# receiver.net
KiCad netlist of a schematic drawn in EAGLE
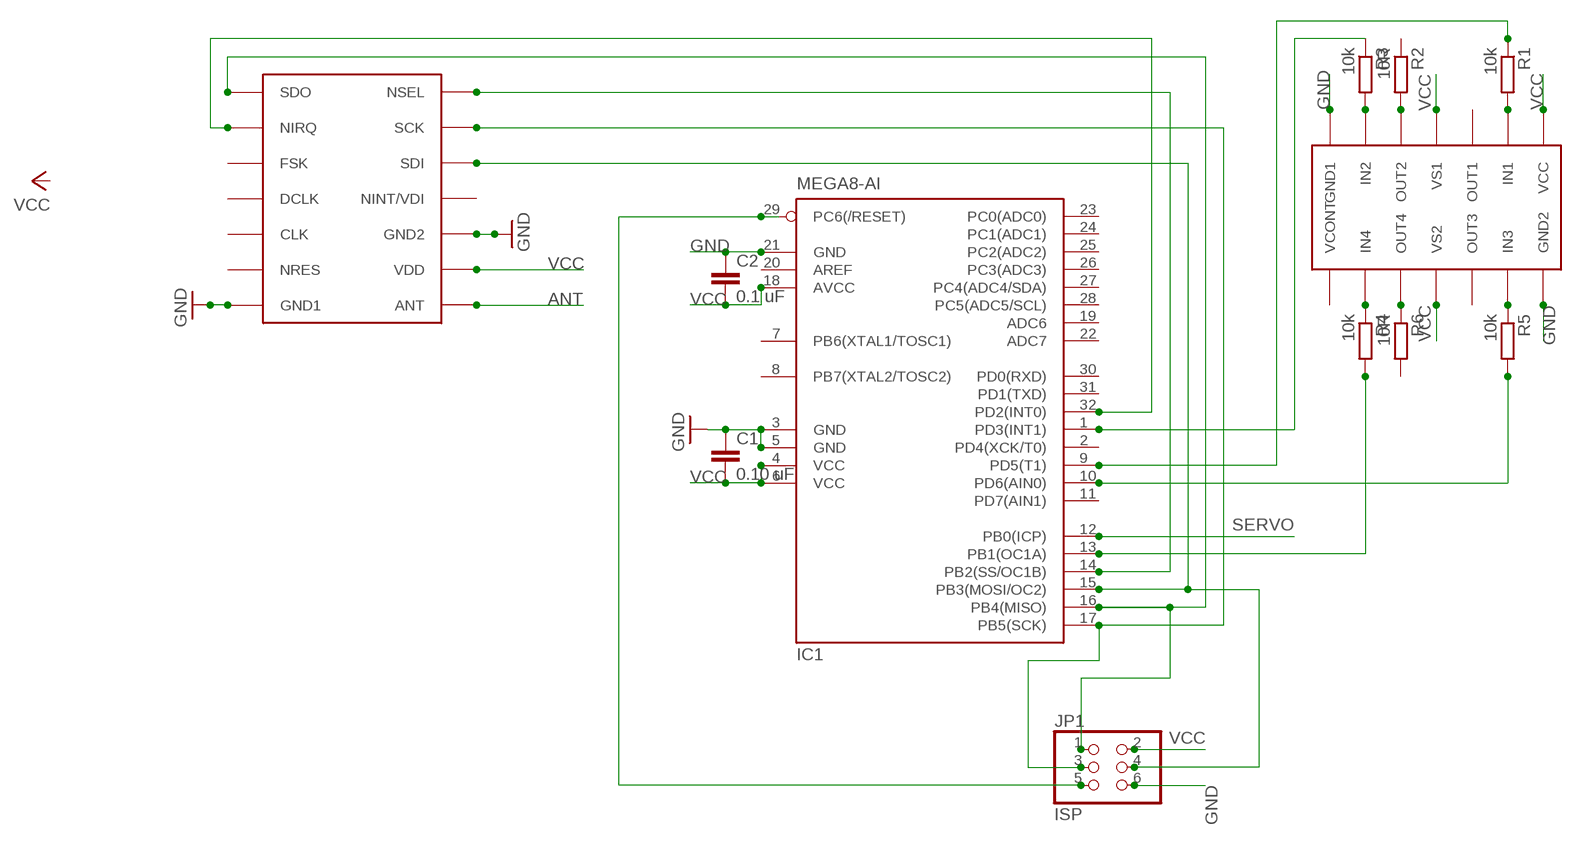
[diagram p0: schematic, sheet 1]

(export (version "E")
  (design (tool "Eeschema 10.0.6"))
  (components
    (comp (ref "C1")
      (value "0.10 uF")
      (footprint "eagle-import:C0805")
      (libsource (lib "eagle-import") (part "C-EUC0805"))
    )
    (comp (ref "C2")
      (value "0.1 uF")
      (footprint "eagle-import:C0805")
      (libsource (lib "eagle-import") (part "C-EUC0805"))
    )
    (comp (ref "IC1")
      (value "MEGA8-AI")
      (footprint "eagle-import:TQFP32-08")
      (fields (field (name "MPN") "ATMEGA8-16AU"))
      (libsource (lib "eagle-import") (part "MEGA8-AI"))
    )
    (comp (ref "JP1")
      (value "ISP")
      (footprint "eagle-import:2X03")
      (libsource (lib "eagle-import") (part "PINHD-2X3"))
    )
    (comp (ref "LB1836M")
      (value "LB1836M")
      (footprint "eagle-import:MFP-14")
      (libsource (lib "eagle-import") (part "LB1836M"))
    )
    (comp (ref "R1")
      (value "10k")
      (footprint "eagle-import:R2012")
      (libsource (lib "eagle-import") (part "R-EU_R2012"))
    )
    (comp (ref "R2")
      (value "10R")
      (footprint "eagle-import:R2012")
      (libsource (lib "eagle-import") (part "R-EU_R2012"))
    )
    (comp (ref "R3")
      (value "10k")
      (footprint "eagle-import:R2012")
      (libsource (lib "eagle-import") (part "R-EU_R2012"))
    )
    (comp (ref "R4")
      (value "10k")
      (footprint "eagle-import:R2012")
      (libsource (lib "eagle-import") (part "R-EU_R2012"))
    )
    (comp (ref "R5")
      (value "10k")
      (footprint "eagle-import:R2012")
      (libsource (lib "eagle-import") (part "R-EU_R2012"))
    )
    (comp (ref "R6")
      (value "10R")
      (footprint "eagle-import:R2012")
      (libsource (lib "eagle-import") (part "R-EU_R2012"))
    )
    (comp (ref "RFM12B")
      (value "RFM12B")
      (footprint "eagle-import:RFM12B")
      (libsource (lib "eagle-import") (part "RFM12B"))
    )
  )
  (nets
    (net (code "1") (name "/ANT") (class "Default")
      (node (ref "RFM12B") (pin "ANT") (pinfunction "ANT_ANT") (pintype "bidirectional"))
    )
    (net (code "2") (name "/SERVO") (class "Default")
      (node (ref "IC1") (pin "12") (pinfunction "PB0(ICP)_12") (pintype "bidirectional"))
    )
    (net (code "3") (name "GND") (class "Default")
      (node (ref "C1") (pin "1") (pinfunction "1_1") (pintype "passive"))
      (node (ref "C2") (pin "1") (pinfunction "1_1") (pintype "passive"))
      (node (ref "IC1") (pin "21") (pinfunction "GND_21") (pintype "power_in"))
      (node (ref "IC1") (pin "3") (pinfunction "GND_3") (pintype "power_in"))
      (node (ref "IC1") (pin "5") (pinfunction "GND_5") (pintype "power_in"))
      (node (ref "JP1") (pin "6") (pinfunction "6_6") (pintype "passive"))
      (node (ref "LB1836M") (pin "GN2") (pinfunction "GND2_GN2") (pintype "bidirectional"))
      (node (ref "LB1836M") (pin "GND1") (pinfunction "GND1_GND1") (pintype "bidirectional"))
      (node (ref "RFM12B") (pin "GND1") (pinfunction "GND1_GND1") (pintype "bidirectional"))
      (node (ref "RFM12B") (pin "GND2") (pinfunction "GND2_GND2") (pintype "bidirectional"))
    )
    (net (code "4") (name "Net-(IC1-PB1(OC1A))") (class "Default")
      (node (ref "IC1") (pin "13") (pinfunction "PB1(OC1A)_13") (pintype "bidirectional"))
      (node (ref "R4") (pin "2") (pinfunction "2_2") (pintype "passive"))
    )
    (net (code "5") (name "Net-(IC1-PB2(SS{slash}OC1B))") (class "Default")
      (node (ref "IC1") (pin "14") (pinfunction "PB2(SS/OC1B)_14") (pintype "bidirectional"))
      (node (ref "RFM12B") (pin "NSEL") (pinfunction "NSEL_NSEL") (pintype "bidirectional"))
    )
    (net (code "6") (name "Net-(IC1-PB3(MOSI{slash}OC2))") (class "Default")
      (node (ref "IC1") (pin "15") (pinfunction "PB3(MOSI/OC2)_15") (pintype "bidirectional"))
      (node (ref "JP1") (pin "4") (pinfunction "4_4") (pintype "passive"))
      (node (ref "RFM12B") (pin "SDI") (pinfunction "SDI_SDI") (pintype "bidirectional"))
    )
    (net (code "7") (name "Net-(IC1-PB4(MISO))") (class "Default")
      (node (ref "IC1") (pin "16") (pinfunction "PB4(MISO)_16") (pintype "bidirectional"))
      (node (ref "JP1") (pin "1") (pinfunction "1_1") (pintype "passive"))
      (node (ref "RFM12B") (pin "SDO") (pinfunction "SDO_SDO") (pintype "bidirectional"))
    )
    (net (code "8") (name "Net-(IC1-PB5(SCK))") (class "Default")
      (node (ref "IC1") (pin "17") (pinfunction "PB5(SCK)_17") (pintype "bidirectional"))
      (node (ref "JP1") (pin "3") (pinfunction "3_3") (pintype "passive"))
      (node (ref "RFM12B") (pin "SCK") (pinfunction "SCK_SCK") (pintype "bidirectional"))
    )
    (net (code "9") (name "Net-(IC1-PC6({slash}RESET))") (class "Default")
      (node (ref "IC1") (pin "29") (pinfunction "PC6(/RESET)_29") (pintype "bidirectional"))
      (node (ref "JP1") (pin "5") (pinfunction "5_5") (pintype "passive"))
    )
    (net (code "10") (name "Net-(IC1-PD2(INT0))") (class "Default")
      (node (ref "IC1") (pin "32") (pinfunction "PD2(INT0)_32") (pintype "bidirectional"))
      (node (ref "RFM12B") (pin "NIRQ") (pinfunction "NIRQ_NIRQ") (pintype "bidirectional"))
    )
    (net (code "11") (name "Net-(IC1-PD3(INT1))") (class "Default")
      (node (ref "IC1") (pin "1") (pinfunction "PD3(INT1)_1") (pintype "bidirectional"))
      (node (ref "R3") (pin "1") (pinfunction "1_1") (pintype "passive"))
    )
    (net (code "12") (name "Net-(IC1-PD5(T1))") (class "Default")
      (node (ref "IC1") (pin "9") (pinfunction "PD5(T1)_9") (pintype "bidirectional"))
      (node (ref "R1") (pin "1") (pinfunction "1_1") (pintype "passive"))
    )
    (net (code "13") (name "Net-(IC1-PD6(AIN0))") (class "Default")
      (node (ref "IC1") (pin "10") (pinfunction "PD6(AIN0)_10") (pintype "bidirectional"))
      (node (ref "R5") (pin "2") (pinfunction "2_2") (pintype "passive"))
    )
    (net (code "14") (name "Net-(LB1836M-PadIN1)") (class "Default")
      (node (ref "LB1836M") (pin "IN1") (pinfunction "IN1_IN1") (pintype "bidirectional"))
      (node (ref "R1") (pin "2") (pinfunction "2_2") (pintype "passive"))
    )
    (net (code "15") (name "Net-(LB1836M-PadIN2)") (class "Default")
      (node (ref "LB1836M") (pin "IN2") (pinfunction "IN2_IN2") (pintype "bidirectional"))
      (node (ref "R3") (pin "2") (pinfunction "2_2") (pintype "passive"))
    )
    (net (code "16") (name "Net-(LB1836M-PadIN3)") (class "Default")
      (node (ref "LB1836M") (pin "IN3") (pinfunction "IN3_IN3") (pintype "bidirectional"))
      (node (ref "R5") (pin "1") (pinfunction "1_1") (pintype "passive"))
    )
    (net (code "17") (name "Net-(LB1836M-PadIN4)") (class "Default")
      (node (ref "LB1836M") (pin "IN4") (pinfunction "IN4_IN4") (pintype "bidirectional"))
      (node (ref "R4") (pin "1") (pinfunction "1_1") (pintype "passive"))
    )
    (net (code "18") (name "Net-(LB1836M-PadOUT2)") (class "Default")
      (node (ref "LB1836M") (pin "OUT2") (pinfunction "OUT2_OUT2") (pintype "bidirectional"))
      (node (ref "R2") (pin "2") (pinfunction "2_2") (pintype "passive"))
    )
    (net (code "19") (name "Net-(LB1836M-PadOUT4)") (class "Default")
      (node (ref "LB1836M") (pin "OUT4") (pinfunction "OUT4_OUT4") (pintype "bidirectional"))
      (node (ref "R6") (pin "1") (pinfunction "1_1") (pintype "passive"))
    )
    (net (code "20") (name "VCC") (class "Default")
      (node (ref "C1") (pin "2") (pinfunction "2_2") (pintype "passive"))
      (node (ref "C2") (pin "2") (pinfunction "2_2") (pintype "passive"))
      (node (ref "IC1") (pin "18") (pinfunction "AVCC_18") (pintype "power_in"))
      (node (ref "IC1") (pin "4") (pinfunction "VCC_4") (pintype "power_in"))
      (node (ref "IC1") (pin "6") (pinfunction "VCC_6") (pintype "power_in"))
      (node (ref "JP1") (pin "2") (pinfunction "2_2") (pintype "passive"))
      (node (ref "LB1836M") (pin "VCC") (pinfunction "VCC_VCC") (pintype "bidirectional"))
      (node (ref "LB1836M") (pin "VS1") (pinfunction "VS1_VS1") (pintype "bidirectional"))
      (node (ref "LB1836M") (pin "VS2") (pinfunction "VS2_VS2") (pintype "bidirectional"))
      (node (ref "RFM12B") (pin "VDD") (pinfunction "VDD_VDD") (pintype "bidirectional"))
    )
    (net (code "21") (name "unconnected-(IC1-ADC6-Pad19)") (class "Default")
      (node (ref "IC1") (pin "19") (pinfunction "ADC6_19") (pintype "bidirectional"))
    )
    (net (code "22") (name "unconnected-(IC1-ADC7-Pad22)") (class "Default")
      (node (ref "IC1") (pin "22") (pinfunction "ADC7_22") (pintype "bidirectional"))
    )
    (net (code "23") (name "unconnected-(IC1-AREF-Pad20)") (class "Default")
      (node (ref "IC1") (pin "20") (pinfunction "AREF_20") (pintype "passive"))
    )
    (net (code "24") (name "unconnected-(IC1-PB6(XTAL1{slash}TOSC1)-Pad7)") (class "Default")
      (node (ref "IC1") (pin "7") (pinfunction "PB6(XTAL1/TOSC1)_7") (pintype "bidirectional"))
    )
    (net (code "25") (name "unconnected-(IC1-PB7(XTAL2{slash}TOSC2)-Pad8)") (class "Default")
      (node (ref "IC1") (pin "8") (pinfunction "PB7(XTAL2/TOSC2)_8") (pintype "bidirectional"))
    )
    (net (code "26") (name "unconnected-(IC1-PC0(ADC0)-Pad23)") (class "Default")
      (node (ref "IC1") (pin "23") (pinfunction "PC0(ADC0)_23") (pintype "bidirectional"))
    )
    (net (code "27") (name "unconnected-(IC1-PC1(ADC1)-Pad24)") (class "Default")
      (node (ref "IC1") (pin "24") (pinfunction "PC1(ADC1)_24") (pintype "bidirectional"))
    )
    (net (code "28") (name "unconnected-(IC1-PC2(ADC2)-Pad25)") (class "Default")
      (node (ref "IC1") (pin "25") (pinfunction "PC2(ADC2)_25") (pintype "bidirectional"))
    )
    (net (code "29") (name "unconnected-(IC1-PC3(ADC3)-Pad26)") (class "Default")
      (node (ref "IC1") (pin "26") (pinfunction "PC3(ADC3)_26") (pintype "bidirectional"))
    )
    (net (code "30") (name "unconnected-(IC1-PC4(ADC4{slash}SDA)-Pad27)") (class "Default")
      (node (ref "IC1") (pin "27") (pinfunction "PC4(ADC4/SDA)_27") (pintype "bidirectional"))
    )
    (net (code "31") (name "unconnected-(IC1-PC5(ADC5{slash}SCL)-Pad28)") (class "Default")
      (node (ref "IC1") (pin "28") (pinfunction "PC5(ADC5/SCL)_28") (pintype "bidirectional"))
    )
    (net (code "32") (name "unconnected-(IC1-PD0(RXD)-Pad30)") (class "Default")
      (node (ref "IC1") (pin "30") (pinfunction "PD0(RXD)_30") (pintype "bidirectional"))
    )
    (net (code "33") (name "unconnected-(IC1-PD1(TXD)-Pad31)") (class "Default")
      (node (ref "IC1") (pin "31") (pinfunction "PD1(TXD)_31") (pintype "bidirectional"))
    )
    (net (code "34") (name "unconnected-(IC1-PD4(XCK{slash}T0)-Pad2)") (class "Default")
      (node (ref "IC1") (pin "2") (pinfunction "PD4(XCK/T0)_2") (pintype "bidirectional"))
    )
    (net (code "35") (name "unconnected-(IC1-PD7(AIN1)-Pad11)") (class "Default")
      (node (ref "IC1") (pin "11") (pinfunction "PD7(AIN1)_11") (pintype "bidirectional"))
    )
    (net (code "36") (name "unconnected-(LB1836M-PadOUT1)") (class "Default")
      (node (ref "LB1836M") (pin "OUT1") (pinfunction "OUT1_OUT1") (pintype "bidirectional"))
    )
    (net (code "37") (name "unconnected-(LB1836M-PadOUT3)") (class "Default")
      (node (ref "LB1836M") (pin "OUT3") (pinfunction "OUT3_OUT3") (pintype "bidirectional"))
    )
    (net (code "38") (name "unconnected-(LB1836M-PadVCONT)") (class "Default")
      (node (ref "LB1836M") (pin "VCONT") (pinfunction "VCONT_VCONT") (pintype "bidirectional"))
    )
    (net (code "39") (name "unconnected-(R2-Pad1)") (class "Default")
      (node (ref "R2") (pin "1") (pinfunction "1_1") (pintype "passive"))
    )
    (net (code "40") (name "unconnected-(R6-Pad2)") (class "Default")
      (node (ref "R6") (pin "2") (pinfunction "2_2") (pintype "passive"))
    )
    (net (code "41") (name "unconnected-(RFM12B-DCLK-PadDCLK{slash}CFIL{slash}FFIT)") (class "Default")
      (node (ref "RFM12B") (pin "DCLK/CFIL/FFIT") (pinfunction "DCLK_DCLK/CFIL/FFIT") (pintype "bidirectional"))
    )
    (net (code "42") (name "unconnected-(RFM12B-FSK-PadFSK{slash}DATA{slash}NFFS)") (class "Default")
      (node (ref "RFM12B") (pin "FSK/DATA/NFFS") (pinfunction "FSK_FSK/DATA/NFFS") (pintype "bidirectional"))
    )
    (net (code "43") (name "unconnected-(RFM12B-PadCLK)") (class "Default")
      (node (ref "RFM12B") (pin "CLK") (pinfunction "CLK_CLK") (pintype "bidirectional"))
    )
    (net (code "44") (name "unconnected-(RFM12B-PadNINT{slash}VDI)") (class "Default")
      (node (ref "RFM12B") (pin "NINT/VDI") (pinfunction "NINT/VDI_NINT/VDI") (pintype "bidirectional"))
    )
    (net (code "45") (name "unconnected-(RFM12B-PadNRES)") (class "Default")
      (node (ref "RFM12B") (pin "NRES") (pinfunction "NRES_NRES") (pintype "bidirectional"))
    )
  )
)
